# InrushTimer.net
KiCad netlist of a schematic drawn in EAGLE
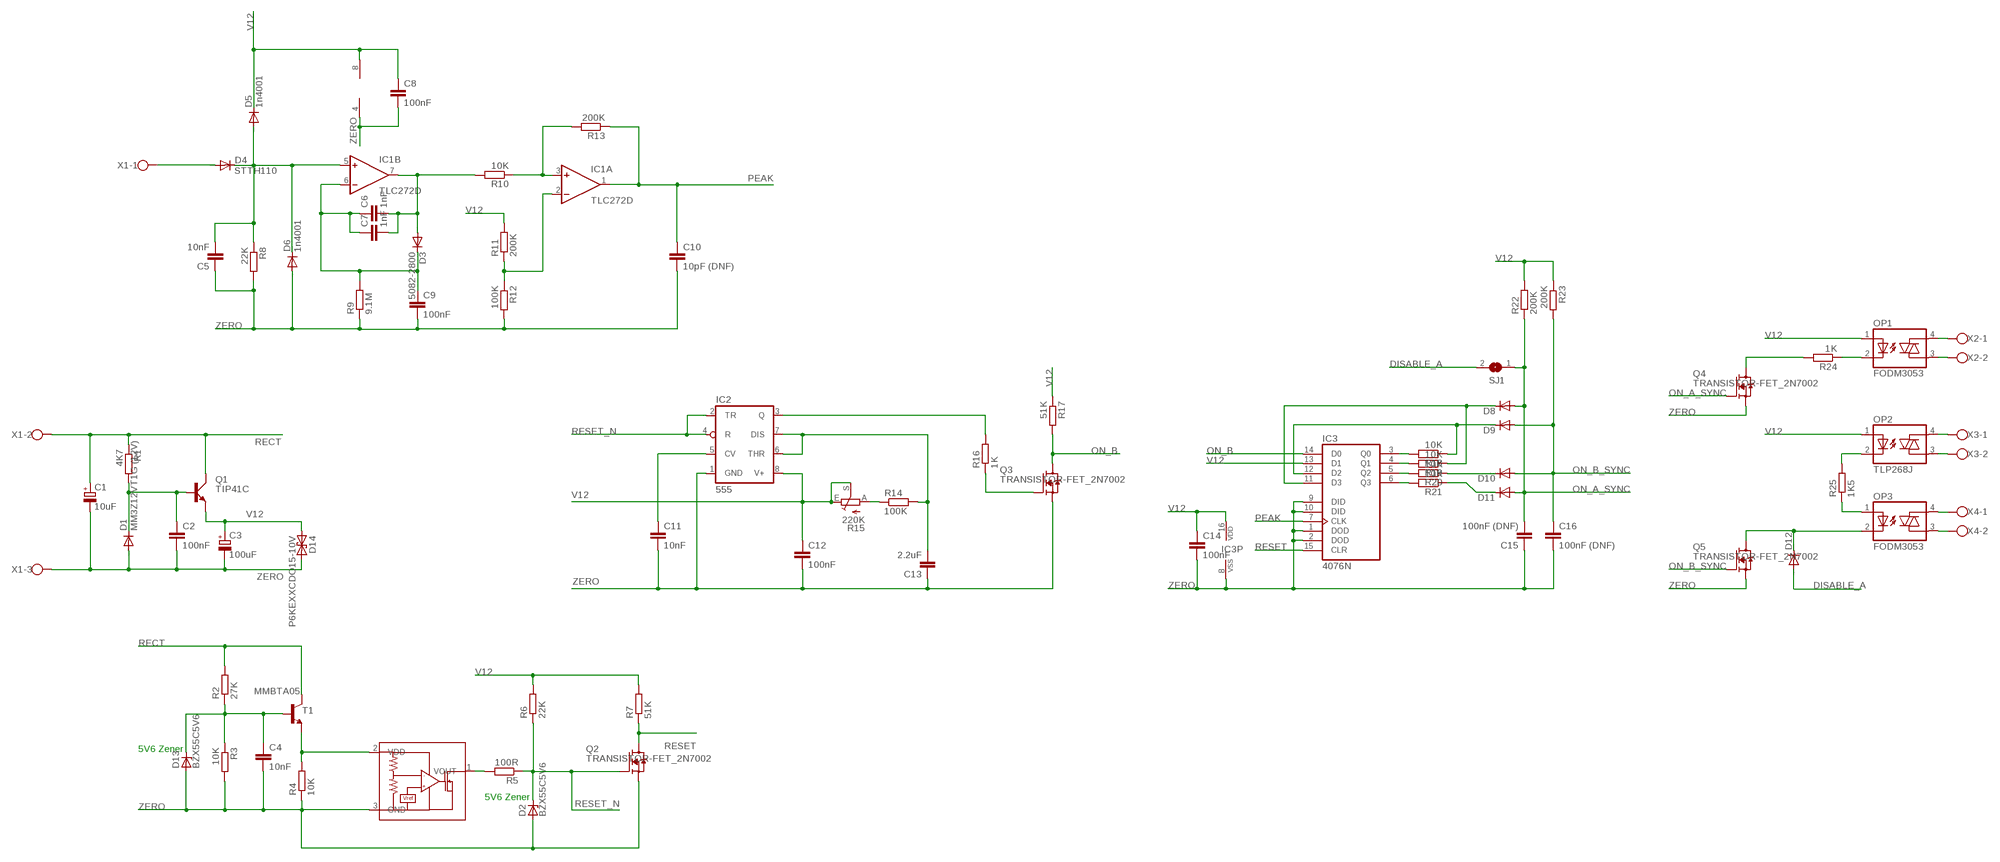
[diagram p0: schematic, sheet 1]

(export (version "E")
  (design (tool "Eeschema 10.0.6"))
  (components
    (comp (ref "C1")
      (value "10uF")
      (footprint "eagle-import:E2-5")
      (libsource (lib "eagle-import") (part "CPOL-EUE2-5"))
    )
    (comp (ref "C2")
      (value "100nF")
      (footprint "eagle-import:C050-024X044")
      (libsource (lib "eagle-import") (part "C-EU050-024X044"))
    )
    (comp (ref "C3")
      (value "100uF")
      (footprint "eagle-import:E2,5-7")
      (libsource (lib "eagle-import") (part "CPOL-EUE2.5-7"))
    )
    (comp (ref "C4")
      (value "10nF")
      (footprint "eagle-import:C050-024X044")
      (libsource (lib "eagle-import") (part "C-EU050-024X044"))
    )
    (comp (ref "C5")
      (value "10nF")
      (footprint "eagle-import:C0805K")
      (libsource (lib "eagle-import") (part "C-EUC0805K"))
    )
    (comp (ref "C6")
      (value "1nF")
      (footprint "eagle-import:C0805K")
      (libsource (lib "eagle-import") (part "C-EUC0805K"))
    )
    (comp (ref "C7")
      (value "1nF")
      (footprint "eagle-import:C0805K")
      (libsource (lib "eagle-import") (part "C-EUC0805K"))
    )
    (comp (ref "C8")
      (value "100nF")
      (footprint "eagle-import:C0805")
      (libsource (lib "eagle-import") (part "C-EUC0805"))
    )
    (comp (ref "C9")
      (value "100nF")
      (footprint "eagle-import:C1206K")
      (libsource (lib "eagle-import") (part "C-EUC1206K"))
    )
    (comp (ref "C10")
      (value "10pF (DNF)")
      (footprint "eagle-import:C0805K")
      (libsource (lib "eagle-import") (part "C-EUC0805K"))
    )
    (comp (ref "C11")
      (value "10nF")
      (footprint "eagle-import:C050-024X044")
      (libsource (lib "eagle-import") (part "C-EU050-024X044"))
    )
    (comp (ref "C12")
      (value "100nF")
      (footprint "eagle-import:C050-024X044")
      (libsource (lib "eagle-import") (part "C-EU050-024X044"))
    )
    (comp (ref "C13")
      (value "2.2uF")
      (footprint "eagle-import:C1206K")
      (libsource (lib "eagle-import") (part "C-EUC1206K"))
    )
    (comp (ref "C14")
      (value "100nF")
      (footprint "eagle-import:C050-024X044")
      (libsource (lib "eagle-import") (part "C-EU050-024X044"))
    )
    (comp (ref "C15")
      (value "100nF (DNF)")
      (footprint "eagle-import:C1206K")
      (libsource (lib "eagle-import") (part "C-EUC1206K"))
    )
    (comp (ref "C16")
      (value "100nF (DNF)")
      (footprint "eagle-import:C1206K")
      (libsource (lib "eagle-import") (part "C-EUC1206K"))
    )
    (comp (ref "D1")
      (value "MM3Z12VT1G (12V)")
      (footprint "eagle-import:SOD323-R")
      (libsource (lib "eagle-import") (part "DIODE-SOD323-R"))
    )
    (comp (ref "D2")
      (value "BZX55C5V6")
      (footprint "eagle-import:DO34Z7")
      (libsource (lib "eagle-import") (part "ZENER-DIODEDO34-7"))
    )
    (comp (ref "D3")
      (value "5082-2800")
      (footprint "eagle-import:DO34-7")
      (libsource (lib "eagle-import") (part "DIODE-DO34-7"))
    )
    (comp (ref "D4")
      (value "STTH110")
      (footprint "eagle-import:DO41-7.6")
      (libsource (lib "eagle-import") (part "DIODE-DO41-7.6"))
    )
    (comp (ref "D5")
      (value "1n4001")
      (footprint "eagle-import:DO41-10VN")
      (libsource (lib "eagle-import") (part "DIODE-DO41-10VN"))
    )
    (comp (ref "D6")
      (value "1n4001")
      (footprint "eagle-import:DO41-7.6")
      (libsource (lib "eagle-import") (part "DIODE-DO41-7.6"))
    )
    (comp (ref "D8")
      (value "1N4148DO35-10")
      (footprint "eagle-import:DO35-10")
      (libsource (lib "eagle-import") (part "1N4148DO35-10"))
    )
    (comp (ref "D9")
      (value "1N4148DO35-7")
      (footprint "eagle-import:DO35-7")
      (libsource (lib "eagle-import") (part "1N4148DO35-7"))
    )
    (comp (ref "D10")
      (value "1N4148DO35-7")
      (footprint "eagle-import:DO35-7")
      (libsource (lib "eagle-import") (part "1N4148DO35-7"))
    )
    (comp (ref "D11")
      (value "1N4148DO35-7")
      (footprint "eagle-import:DO35-7")
      (libsource (lib "eagle-import") (part "1N4148DO35-7"))
    )
    (comp (ref "D12")
      (value "1N4148DO35-7")
      (footprint "eagle-import:DO35-7")
      (libsource (lib "eagle-import") (part "1N4148DO35-7"))
    )
    (comp (ref "D13")
      (value "BZX55C5V6")
      (footprint "eagle-import:DO34Z7")
      (libsource (lib "eagle-import") (part "ZENER-DIODEDO34-7"))
    )
    (comp (ref "D14")
      (value "P6KEXXCDO15-10V")
      (footprint "eagle-import:DO15-10V")
      (libsource (lib "eagle-import") (part "P6KEXXCDO15-10V"))
    )
    (comp (ref "IC1")
      (value "TLC272D")
      (footprint "eagle-import:SO08")
      (libsource (lib "eagle-import") (part "TLC272D"))
    )
    (comp (ref "IC2")
      (value "555")
      (footprint "eagle-import:SO08-555")
      (libsource (lib "eagle-import") (part "555"))
    )
    (comp (ref "IC3")
      (value "4076N")
      (footprint "eagle-import:DIL16")
      (libsource (lib "eagle-import") (part "4076N"))
    )
    (comp (ref "OP1")
      (value "FODM3053")
      (footprint "eagle-import:FODM")
      (libsource (lib "eagle-import") (part "FODM3053"))
    )
    (comp (ref "OP2")
      (value "TLP268J")
      (footprint "eagle-import:TLP26_")
      (libsource (lib "eagle-import") (part "TLP268J"))
    )
    (comp (ref "OP3")
      (value "FODM3053")
      (footprint "eagle-import:FODM")
      (libsource (lib "eagle-import") (part "FODM3053"))
    )
    (comp (ref "Q1")
      (value "TIP41C")
      (footprint "eagle-import:TO220AV")
      (libsource (lib "eagle-import") (part "TIP41C"))
    )
    (comp (ref "Q2")
      (value "TRANSISTOR-FET_2N7002")
      (footprint "eagle-import:TRANSISTOR-FET_SOT23")
      (libsource (lib "eagle-import") (part "TRANSISTOR-FET_2N7002"))
    )
    (comp (ref "Q3")
      (value "TRANSISTOR-FET_2N7002")
      (footprint "eagle-import:TRANSISTOR-FET_SOT23")
      (libsource (lib "eagle-import") (part "TRANSISTOR-FET_2N7002"))
    )
    (comp (ref "Q4")
      (value "TRANSISTOR-FET_2N7002")
      (footprint "eagle-import:TRANSISTOR-FET_SOT23")
      (libsource (lib "eagle-import") (part "TRANSISTOR-FET_2N7002"))
    )
    (comp (ref "Q5")
      (value "TRANSISTOR-FET_2N7002")
      (footprint "eagle-import:TRANSISTOR-FET_SOT23")
      (libsource (lib "eagle-import") (part "TRANSISTOR-FET_2N7002"))
    )
    (comp (ref "R1")
      (value "4K7")
      (footprint "eagle-import:0207_2V")
      (libsource (lib "eagle-import") (part "R-EU_0207/2V"))
    )
    (comp (ref "R2")
      (value "27K")
      (footprint "eagle-import:0207_7")
      (libsource (lib "eagle-import") (part "R-EU_0207/7"))
    )
    (comp (ref "R3")
      (value "10K")
      (footprint "eagle-import:0207_2V")
      (libsource (lib "eagle-import") (part "R-EU_0207/2V"))
    )
    (comp (ref "R4")
      (value "10K")
      (footprint "eagle-import:R0805")
      (libsource (lib "eagle-import") (part "R-EU_R0805"))
    )
    (comp (ref "R5")
      (value "100R")
      (footprint "eagle-import:0207_7")
      (libsource (lib "eagle-import") (part "R-EU_0207/7"))
    )
    (comp (ref "R6")
      (value "22K")
      (footprint "eagle-import:0207_2V")
      (libsource (lib "eagle-import") (part "R-EU_0207/2V"))
    )
    (comp (ref "R7")
      (value "51K")
      (footprint "eagle-import:0207_2V")
      (libsource (lib "eagle-import") (part "R-EU_0207/2V"))
    )
    (comp (ref "R8")
      (value "22K")
      (footprint "eagle-import:0207_2V")
      (libsource (lib "eagle-import") (part "R-EU_0207/2V"))
    )
    (comp (ref "R9")
      (value "9.1M")
      (footprint "eagle-import:0207_7")
      (libsource (lib "eagle-import") (part "R-EU_0207/7"))
    )
    (comp (ref "R10")
      (value "10K")
      (footprint "eagle-import:0207_10")
      (libsource (lib "eagle-import") (part "R-EU_0207/10"))
    )
    (comp (ref "R11")
      (value "200K")
      (footprint "eagle-import:0207_2V")
      (libsource (lib "eagle-import") (part "R-EU_0207/2V"))
    )
    (comp (ref "R12")
      (value "100K")
      (footprint "eagle-import:0207_2V")
      (libsource (lib "eagle-import") (part "R-EU_0207/2V"))
    )
    (comp (ref "R13")
      (value "200K")
      (footprint "eagle-import:0207_2V")
      (libsource (lib "eagle-import") (part "R-EU_0207/2V"))
    )
    (comp (ref "R14")
      (value "100K")
      (footprint "eagle-import:0207_2V")
      (libsource (lib "eagle-import") (part "R-EU_0207/2V"))
    )
    (comp (ref "R15")
      (value "220K")
      (footprint "eagle-import:CA6H")
      (libsource (lib "eagle-import") (part "TRIM_EU-CA6H"))
    )
    (comp (ref "R16")
      (value "1K")
      (footprint "eagle-import:R0402")
      (libsource (lib "eagle-import") (part "R-EU_R0402"))
    )
    (comp (ref "R17")
      (value "51K")
      (footprint "eagle-import:0207_2V")
      (libsource (lib "eagle-import") (part "R-EU_0207/2V"))
    )
    (comp (ref "R18")
      (value "10K")
      (footprint "eagle-import:R0805")
      (libsource (lib "eagle-import") (part "R-EU_R0805"))
    )
    (comp (ref "R19")
      (value "10K")
      (footprint "eagle-import:R0805")
      (libsource (lib "eagle-import") (part "R-EU_R0805"))
    )
    (comp (ref "R20")
      (value "10K")
      (footprint "eagle-import:R0805")
      (libsource (lib "eagle-import") (part "R-EU_R0805"))
    )
    (comp (ref "R21")
      (value "10K")
      (footprint "eagle-import:R0805")
      (libsource (lib "eagle-import") (part "R-EU_R0805"))
    )
    (comp (ref "R22")
      (value "200K")
      (footprint "eagle-import:0207_2V")
      (libsource (lib "eagle-import") (part "R-EU_0207/2V"))
    )
    (comp (ref "R23")
      (value "200K")
      (footprint "eagle-import:0207_7")
      (libsource (lib "eagle-import") (part "R-EU_0207/7"))
    )
    (comp (ref "R24")
      (value "1K")
      (footprint "eagle-import:0207_7")
      (libsource (lib "eagle-import") (part "R-EU_0207/7"))
    )
    (comp (ref "R25")
      (value "1K5")
      (footprint "eagle-import:0207_2V")
      (libsource (lib "eagle-import") (part "R-EU_0207/2V"))
    )
    (comp (ref "SJ1") (value "SJ") (footprint "eagle-import:SJ") (libsource (lib "eagle-import") (part "SJ")))
    (comp (ref "T1")
      (value "MMBTA05")
      (footprint "eagle-import:SOT23-BEC")
      (libsource (lib "eagle-import") (part "-NPN-SOT23-BECMMBTA42LT1"))
    )
    (comp (ref "U1")
      (value "ROHM_BY_ELEMENT14_BATCH_1_BU48XXG")
      (footprint "eagle-import:ROHM_BY_ELEMENT14_BATCH_1_SOT95P280X125-5N")
      (libsource (lib "eagle-import") (part "ROHM_BY_ELEMENT14_BATCH_1_BU48XXG"))
    )
    (comp (ref "X1")
      (value "W237-103")
      (footprint "eagle-import:W237-103")
      (fields (field (name "MPN") "237-103"))
      (libsource (lib "eagle-import") (part "W237-103"))
    )
    (comp (ref "X2")
      (value "W237-102")
      (footprint "eagle-import:W237-102")
      (fields (field (name "MPN") "237-102"))
      (libsource (lib "eagle-import") (part "W237-102"))
    )
    (comp (ref "X3")
      (value "W237-102")
      (footprint "eagle-import:W237-102")
      (fields (field (name "MPN") "237-102"))
      (libsource (lib "eagle-import") (part "W237-102"))
    )
    (comp (ref "X4")
      (value "W237-102")
      (footprint "eagle-import:W237-102")
      (fields (field (name "MPN") "237-102"))
      (libsource (lib "eagle-import") (part "W237-102"))
    )
  )
  (nets
    (net (code "1") (name "/DISABLE_A") (class "Default")
      (node (ref "D12") (pin "A") (pinfunction "A_A") (pintype "passive"))
      (node (ref "SJ1") (pin "2") (pinfunction "2_2") (pintype "passive"))
    )
    (net (code "2") (name "/ON_A_SYNC") (class "Default")
      (node (ref "C15") (pin "2") (pinfunction "2_2") (pintype "passive"))
      (node (ref "D11") (pin "A") (pinfunction "A_A") (pintype "passive"))
      (node (ref "D8") (pin "A") (pinfunction "A_A") (pintype "passive"))
      (node (ref "Q4") (pin "1") (pinfunction "G_1") (pintype "passive"))
      (node (ref "R22") (pin "1") (pinfunction "1_1") (pintype "passive"))
      (node (ref "SJ1") (pin "1") (pinfunction "1_1") (pintype "passive"))
    )
    (net (code "3") (name "/ON_B") (class "Default")
      (node (ref "IC3") (pin "14") (pinfunction "D0_14") (pintype "input"))
      (node (ref "Q3") (pin "3") (pinfunction "D_3") (pintype "passive"))
      (node (ref "R17") (pin "2") (pinfunction "2_2") (pintype "passive"))
    )
    (net (code "4") (name "/ON_B_SYNC") (class "Default")
      (node (ref "C16") (pin "1") (pinfunction "1_1") (pintype "passive"))
      (node (ref "D10") (pin "A") (pinfunction "A_A") (pintype "passive"))
      (node (ref "D9") (pin "A") (pinfunction "A_A") (pintype "passive"))
      (node (ref "Q5") (pin "1") (pinfunction "G_1") (pintype "passive"))
      (node (ref "R23") (pin "2") (pinfunction "2_2") (pintype "passive"))
    )
    (net (code "5") (name "/PEAK") (class "Default")
      (node (ref "C10") (pin "1") (pinfunction "1_1") (pintype "passive"))
      (node (ref "IC1") (pin "1") (pinfunction "OUT_1") (pintype "output"))
      (node (ref "IC3") (pin "7") (pinfunction "CLK_7") (pintype "input"))
      (node (ref "R13") (pin "1") (pinfunction "1_1") (pintype "passive"))
    )
    (net (code "6") (name "/RECT") (class "Default")
      (node (ref "C1") (pin "+") (pinfunction "+_+") (pintype "passive"))
      (node (ref "Q1") (pin "C") (pinfunction "C_C") (pintype "passive"))
      (node (ref "R1") (pin "1") (pinfunction "1_1") (pintype "passive"))
      (node (ref "R2") (pin "2") (pinfunction "2_2") (pintype "passive"))
      (node (ref "T1") (pin "C") (pinfunction "C_C") (pintype "passive"))
      (node (ref "X1") (pin "2") (pinfunction "KL_2") (pintype "passive"))
    )
    (net (code "7") (name "/RESET") (class "Default")
      (node (ref "IC3") (pin "15") (pinfunction "CLR_15") (pintype "input"))
      (node (ref "Q2") (pin "3") (pinfunction "D_3") (pintype "passive"))
      (node (ref "R7") (pin "1") (pinfunction "1_1") (pintype "passive"))
    )
    (net (code "8") (name "/RESET_N") (class "Default")
      (node (ref "D2") (pin "C") (pinfunction "C_C") (pintype "passive"))
      (node (ref "IC2") (pin "2") (pinfunction "TR_2") (pintype "input"))
      (node (ref "IC2") (pin "4") (pinfunction "R_4") (pintype "input"))
      (node (ref "Q2") (pin "1") (pinfunction "G_1") (pintype "passive"))
      (node (ref "R5") (pin "1") (pinfunction "1_1") (pintype "passive"))
      (node (ref "R6") (pin "1") (pinfunction "1_1") (pintype "passive"))
    )
    (net (code "9") (name "/V12") (class "Default")
      (node (ref "C12") (pin "1") (pinfunction "1_1") (pintype "passive"))
      (node (ref "C14") (pin "1") (pinfunction "1_1") (pintype "passive"))
      (node (ref "C3") (pin "+") (pinfunction "+_+") (pintype "passive"))
      (node (ref "C8") (pin "1") (pinfunction "1_1") (pintype "passive"))
      (node (ref "D14") (pin "A") (pinfunction "1_A") (pintype "passive"))
      (node (ref "D5") (pin "C") (pinfunction "C_C") (pintype "passive"))
      (node (ref "IC1") (pin "8") (pinfunction "V+_8") (pintype "power_in"))
      (node (ref "IC2") (pin "8") (pinfunction "V+_8") (pintype "power_in"))
      (node (ref "IC3") (pin "13") (pinfunction "D1_13") (pintype "input"))
      (node (ref "IC3") (pin "16") (pinfunction "VDD_16") (pintype "power_in"))
      (node (ref "OP1") (pin "1") (pinfunction "A_1") (pintype "passive"))
      (node (ref "OP2") (pin "1") (pinfunction "A_1") (pintype "passive"))
      (node (ref "Q1") (pin "E") (pinfunction "E_E") (pintype "passive"))
      (node (ref "R11") (pin "2") (pinfunction "2_2") (pintype "passive"))
      (node (ref "R15") (pin "E") (pinfunction "E_E") (pintype "passive"))
      (node (ref "R15") (pin "S") (pinfunction "S_S") (pintype "passive"))
      (node (ref "R17") (pin "1") (pinfunction "1_1") (pintype "passive"))
      (node (ref "R22") (pin "2") (pinfunction "2_2") (pintype "passive"))
      (node (ref "R23") (pin "1") (pinfunction "1_1") (pintype "passive"))
      (node (ref "R6") (pin "2") (pinfunction "2_2") (pintype "passive"))
      (node (ref "R7") (pin "2") (pinfunction "2_2") (pintype "passive"))
    )
    (net (code "10") (name "/ZERO") (class "Default")
      (node (ref "C1") (pin "-") (pinfunction "-_-") (pintype "passive"))
      (node (ref "C10") (pin "2") (pinfunction "2_2") (pintype "passive"))
      (node (ref "C11") (pin "2") (pinfunction "2_2") (pintype "passive"))
      (node (ref "C12") (pin "2") (pinfunction "2_2") (pintype "passive"))
      (node (ref "C13") (pin "1") (pinfunction "1_1") (pintype "passive"))
      (node (ref "C14") (pin "2") (pinfunction "2_2") (pintype "passive"))
      (node (ref "C15") (pin "1") (pinfunction "1_1") (pintype "passive"))
      (node (ref "C16") (pin "2") (pinfunction "2_2") (pintype "passive"))
      (node (ref "C2") (pin "2") (pinfunction "2_2") (pintype "passive"))
      (node (ref "C3") (pin "-") (pinfunction "-_-") (pintype "passive"))
      (node (ref "C4") (pin "2") (pinfunction "2_2") (pintype "passive"))
      (node (ref "C5") (pin "1") (pinfunction "1_1") (pintype "passive"))
      (node (ref "C8") (pin "2") (pinfunction "2_2") (pintype "passive"))
      (node (ref "C9") (pin "2") (pinfunction "2_2") (pintype "passive"))
      (node (ref "D1") (pin "A") (pinfunction "A_A") (pintype "passive"))
      (node (ref "D13") (pin "A") (pinfunction "A_A") (pintype "passive"))
      (node (ref "D14") (pin "C") (pinfunction "2_C") (pintype "passive"))
      (node (ref "D2") (pin "A") (pinfunction "A_A") (pintype "passive"))
      (node (ref "D6") (pin "A") (pinfunction "A_A") (pintype "passive"))
      (node (ref "IC1") (pin "4") (pinfunction "V-_4") (pintype "power_in"))
      (node (ref "IC2") (pin "1") (pinfunction "GND_1") (pintype "power_in"))
      (node (ref "IC3") (pin "1") (pinfunction "DOD_1") (pintype "input"))
      (node (ref "IC3") (pin "10") (pinfunction "DID_10") (pintype "input"))
      (node (ref "IC3") (pin "2") (pinfunction "DOD_2") (pintype "input"))
      (node (ref "IC3") (pin "8") (pinfunction "VSS_8") (pintype "power_in"))
      (node (ref "IC3") (pin "9") (pinfunction "DID_9") (pintype "input"))
      (node (ref "Q2") (pin "2") (pinfunction "S_2") (pintype "passive"))
      (node (ref "Q3") (pin "2") (pinfunction "S_2") (pintype "passive"))
      (node (ref "Q4") (pin "2") (pinfunction "S_2") (pintype "passive"))
      (node (ref "Q5") (pin "2") (pinfunction "S_2") (pintype "passive"))
      (node (ref "R12") (pin "2") (pinfunction "2_2") (pintype "passive"))
      (node (ref "R3") (pin "2") (pinfunction "2_2") (pintype "passive"))
      (node (ref "R4") (pin "1") (pinfunction "1_1") (pintype "passive"))
      (node (ref "R8") (pin "2") (pinfunction "2_2") (pintype "passive"))
      (node (ref "R9") (pin "1") (pinfunction "1_1") (pintype "passive"))
      (node (ref "U1") (pin "3") (pinfunction "GND_3") (pintype "bidirectional"))
      (node (ref "X1") (pin "3") (pinfunction "KL_3") (pintype "passive"))
    )
    (net (code "11") (name "Net-(C2-Pad1)") (class "Default")
      (node (ref "C2") (pin "1") (pinfunction "1_1") (pintype "passive"))
      (node (ref "D1") (pin "C") (pinfunction "C_C") (pintype "passive"))
      (node (ref "Q1") (pin "B") (pinfunction "B_B") (pintype "passive"))
      (node (ref "R1") (pin "2") (pinfunction "2_2") (pintype "passive"))
    )
    (net (code "12") (name "Net-(C4-Pad1)") (class "Default")
      (node (ref "C4") (pin "1") (pinfunction "1_1") (pintype "passive"))
      (node (ref "D13") (pin "C") (pinfunction "C_C") (pintype "passive"))
      (node (ref "R2") (pin "1") (pinfunction "1_1") (pintype "passive"))
      (node (ref "R3") (pin "1") (pinfunction "1_1") (pintype "passive"))
      (node (ref "T1") (pin "B") (pinfunction "B_B") (pintype "passive"))
    )
    (net (code "13") (name "Net-(D10-PadC)") (class "Default")
      (node (ref "D10") (pin "C") (pinfunction "C_C") (pintype "passive"))
      (node (ref "R20") (pin "1") (pinfunction "1_1") (pintype "passive"))
    )
    (net (code "14") (name "Net-(D11-PadC)") (class "Default")
      (node (ref "D11") (pin "C") (pinfunction "C_C") (pintype "passive"))
      (node (ref "R21") (pin "1") (pinfunction "1_1") (pintype "passive"))
    )
    (net (code "15") (name "Net-(IC1A-+IN)") (class "Default")
      (node (ref "IC1") (pin "3") (pinfunction "+IN_3") (pintype "input"))
      (node (ref "R10") (pin "1") (pinfunction "1_1") (pintype "passive"))
      (node (ref "R13") (pin "2") (pinfunction "2_2") (pintype "passive"))
    )
    (net (code "16") (name "Net-(IC1A--IN)") (class "Default")
      (node (ref "IC1") (pin "2") (pinfunction "-IN_2") (pintype "input"))
      (node (ref "R11") (pin "1") (pinfunction "1_1") (pintype "passive"))
      (node (ref "R12") (pin "1") (pinfunction "1_1") (pintype "passive"))
    )
    (net (code "17") (name "Net-(IC1B-+IN)") (class "Default")
      (node (ref "C5") (pin "2") (pinfunction "2_2") (pintype "passive"))
      (node (ref "D4") (pin "C") (pinfunction "C_C") (pintype "passive"))
      (node (ref "D5") (pin "A") (pinfunction "A_A") (pintype "passive"))
      (node (ref "D6") (pin "C") (pinfunction "C_C") (pintype "passive"))
      (node (ref "IC1") (pin "5") (pinfunction "+IN_5") (pintype "input"))
      (node (ref "R8") (pin "1") (pinfunction "1_1") (pintype "passive"))
    )
    (net (code "18") (name "Net-(IC1B--IN)") (class "Default")
      (node (ref "C6") (pin "1") (pinfunction "1_1") (pintype "passive"))
      (node (ref "C7") (pin "1") (pinfunction "1_1") (pintype "passive"))
      (node (ref "C9") (pin "1") (pinfunction "1_1") (pintype "passive"))
      (node (ref "D3") (pin "C") (pinfunction "C_C") (pintype "passive"))
      (node (ref "IC1") (pin "6") (pinfunction "-IN_6") (pintype "input"))
      (node (ref "R9") (pin "2") (pinfunction "2_2") (pintype "passive"))
    )
    (net (code "19") (name "Net-(IC1B-OUT)") (class "Default")
      (node (ref "C6") (pin "2") (pinfunction "2_2") (pintype "passive"))
      (node (ref "C7") (pin "2") (pinfunction "2_2") (pintype "passive"))
      (node (ref "D3") (pin "A") (pinfunction "A_A") (pintype "passive"))
      (node (ref "IC1") (pin "7") (pinfunction "OUT_7") (pintype "output"))
      (node (ref "R10") (pin "2") (pinfunction "2_2") (pintype "passive"))
    )
    (net (code "20") (name "Net-(IC2-CV)") (class "Default")
      (node (ref "C11") (pin "1") (pinfunction "1_1") (pintype "passive"))
      (node (ref "IC2") (pin "5") (pinfunction "CV_5") (pintype "input"))
    )
    (net (code "21") (name "Net-(IC2-DIS)") (class "Default")
      (node (ref "C13") (pin "2") (pinfunction "2_2") (pintype "passive"))
      (node (ref "IC2") (pin "6") (pinfunction "THR_6") (pintype "input"))
      (node (ref "IC2") (pin "7") (pinfunction "DIS_7") (pintype "input"))
      (node (ref "R14") (pin "2") (pinfunction "2_2") (pintype "passive"))
    )
    (net (code "22") (name "Net-(IC2-Q)") (class "Default")
      (node (ref "IC2") (pin "3") (pinfunction "Q_3") (pintype "output"))
      (node (ref "R16") (pin "2") (pinfunction "2_2") (pintype "passive"))
    )
    (net (code "23") (name "Net-(IC3A-D2)") (class "Default")
      (node (ref "D9") (pin "C") (pinfunction "C_C") (pintype "passive"))
      (node (ref "IC3") (pin "12") (pinfunction "D2_12") (pintype "input"))
      (node (ref "R18") (pin "1") (pinfunction "1_1") (pintype "passive"))
    )
    (net (code "24") (name "Net-(IC3A-D3)") (class "Default")
      (node (ref "D8") (pin "C") (pinfunction "C_C") (pintype "passive"))
      (node (ref "IC3") (pin "11") (pinfunction "D3_11") (pintype "input"))
      (node (ref "R19") (pin "1") (pinfunction "1_1") (pintype "passive"))
    )
    (net (code "25") (name "Net-(IC3A-Q0)") (class "Default")
      (node (ref "IC3") (pin "3") (pinfunction "Q0_3") (pintype "output"))
      (node (ref "R18") (pin "2") (pinfunction "2_2") (pintype "passive"))
    )
    (net (code "26") (name "Net-(IC3A-Q1)") (class "Default")
      (node (ref "IC3") (pin "4") (pinfunction "Q1_4") (pintype "output"))
      (node (ref "R19") (pin "2") (pinfunction "2_2") (pintype "passive"))
    )
    (net (code "27") (name "Net-(IC3A-Q2)") (class "Default")
      (node (ref "IC3") (pin "5") (pinfunction "Q2_5") (pintype "output"))
      (node (ref "R20") (pin "2") (pinfunction "2_2") (pintype "passive"))
    )
    (net (code "28") (name "Net-(IC3A-Q3)") (class "Default")
      (node (ref "IC3") (pin "6") (pinfunction "Q3_6") (pintype "output"))
      (node (ref "R21") (pin "2") (pinfunction "2_2") (pintype "passive"))
    )
    (net (code "29") (name "Net-(OP1-A1)") (class "Default")
      (node (ref "OP1") (pin "3") (pinfunction "A1_3") (pintype "passive"))
      (node (ref "X2") (pin "2") (pinfunction "KL_2") (pintype "passive"))
    )
    (net (code "30") (name "Net-(OP1-A2)") (class "Default")
      (node (ref "OP1") (pin "4") (pinfunction "A2_4") (pintype "passive"))
      (node (ref "X2") (pin "1") (pinfunction "KL_1") (pintype "passive"))
    )
    (net (code "31") (name "Net-(OP1-C)") (class "Default")
      (node (ref "OP1") (pin "2") (pinfunction "C_2") (pintype "passive"))
      (node (ref "R24") (pin "1") (pinfunction "1_1") (pintype "passive"))
    )
    (net (code "32") (name "Net-(OP2-A1)") (class "Default")
      (node (ref "OP2") (pin "3") (pinfunction "A1_3") (pintype "passive"))
      (node (ref "X3") (pin "2") (pinfunction "KL_2") (pintype "passive"))
    )
    (net (code "33") (name "Net-(OP2-A2)") (class "Default")
      (node (ref "OP2") (pin "4") (pinfunction "A2_4") (pintype "passive"))
      (node (ref "X3") (pin "1") (pinfunction "KL_1") (pintype "passive"))
    )
    (net (code "34") (name "Net-(OP2-C)") (class "Default")
      (node (ref "OP2") (pin "2") (pinfunction "C_2") (pintype "passive"))
      (node (ref "R25") (pin "2") (pinfunction "2_2") (pintype "passive"))
    )
    (net (code "35") (name "Net-(OP3-A)") (class "Default")
      (node (ref "OP3") (pin "1") (pinfunction "A_1") (pintype "passive"))
      (node (ref "R25") (pin "1") (pinfunction "1_1") (pintype "passive"))
    )
    (net (code "36") (name "Net-(OP3-A1)") (class "Default")
      (node (ref "OP3") (pin "3") (pinfunction "A1_3") (pintype "passive"))
      (node (ref "X4") (pin "2") (pinfunction "KL_2") (pintype "passive"))
    )
    (net (code "37") (name "Net-(OP3-A2)") (class "Default")
      (node (ref "OP3") (pin "4") (pinfunction "A2_4") (pintype "passive"))
      (node (ref "X4") (pin "1") (pinfunction "KL_1") (pintype "passive"))
    )
    (net (code "38") (name "Net-(OP3-C)") (class "Default")
      (node (ref "D12") (pin "C") (pinfunction "C_C") (pintype "passive"))
      (node (ref "OP3") (pin "2") (pinfunction "C_2") (pintype "passive"))
      (node (ref "Q5") (pin "3") (pinfunction "D_3") (pintype "passive"))
    )
    (net (code "39") (name "Net-(Q3-G)") (class "Default")
      (node (ref "Q3") (pin "1") (pinfunction "G_1") (pintype "passive"))
      (node (ref "R16") (pin "1") (pinfunction "1_1") (pintype "passive"))
    )
    (net (code "40") (name "Net-(Q4-D)") (class "Default")
      (node (ref "Q4") (pin "3") (pinfunction "D_3") (pintype "passive"))
      (node (ref "R24") (pin "2") (pinfunction "2_2") (pintype "passive"))
    )
    (net (code "41") (name "Net-(R14-Pad1)") (class "Default")
      (node (ref "R14") (pin "1") (pinfunction "1_1") (pintype "passive"))
      (node (ref "R15") (pin "A") (pinfunction "A_A") (pintype "passive"))
    )
    (net (code "42") (name "Net-(U1-VDD)") (class "Default")
      (node (ref "R4") (pin "2") (pinfunction "2_2") (pintype "passive"))
      (node (ref "T1") (pin "E") (pinfunction "E_E") (pintype "passive"))
      (node (ref "U1") (pin "2") (pinfunction "VDD_2") (pintype "bidirectional"))
    )
    (net (code "43") (name "Net-(U1-VOUT)") (class "Default")
      (node (ref "R5") (pin "2") (pinfunction "2_2") (pintype "passive"))
      (node (ref "U1") (pin "1") (pinfunction "VOUT_1") (pintype "bidirectional"))
    )
    (net (code "44") (name "Net-(X1A-KL)") (class "Default")
      (node (ref "D4") (pin "A") (pinfunction "A_A") (pintype "passive"))
      (node (ref "X1") (pin "1") (pinfunction "KL_1") (pintype "passive"))
    )
  )
)
